# FiltroRecuperador.net
KiCad netlist of a schematic drawn in Altium Designer
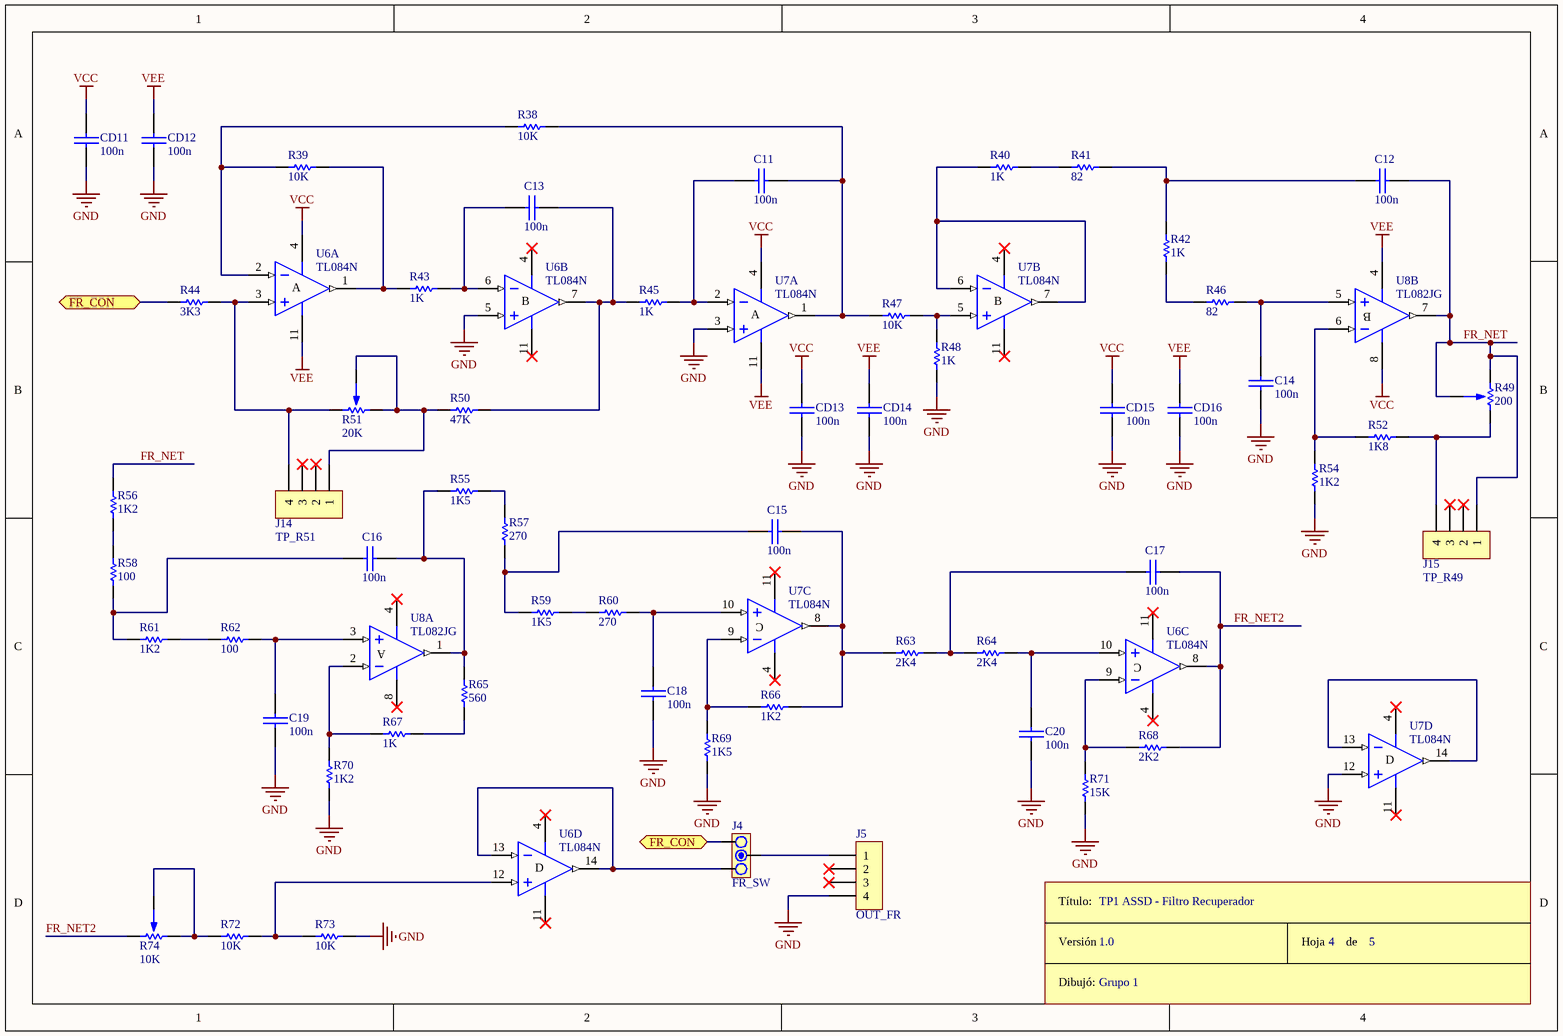
[diagram p0: FiltroRecuperador.SchDoc]

(export (version "E")
  (design (tool "Eeschema 10.0.6"))
  (components
    (comp (ref "C11") (value "100n") (footprint "CAP100") (libsource (lib "LIBEBAL") (part "CAP")))
    (comp (ref "C12") (value "100n") (footprint "CAP100") (libsource (lib "LIBEBAL") (part "CAP")))
    (comp (ref "C13") (value "100n") (footprint "CAP100") (libsource (lib "LIBEBAL") (part "CAP")))
    (comp (ref "C14") (value "100n") (footprint "CAP100") (libsource (lib "LIBEBAL") (part "CAP")))
    (comp (ref "C15") (value "100n") (footprint "CAP100") (libsource (lib "LIBEBAL") (part "CAP")))
    (comp (ref "C16") (value "100n") (footprint "CAP100") (libsource (lib "LIBEBAL") (part "CAP")))
    (comp (ref "C17") (value "100n") (footprint "CAP100") (libsource (lib "LIBEBAL") (part "CAP")))
    (comp (ref "C18") (value "100n") (footprint "CAP100") (libsource (lib "LIBEBAL") (part "CAP")))
    (comp (ref "C19") (value "100n") (footprint "CAP100") (libsource (lib "LIBEBAL") (part "CAP")))
    (comp (ref "C20") (value "100n") (footprint "CAP100") (libsource (lib "LIBEBAL") (part "CAP")))
    (comp (ref "CD11") (value "100n") (footprint "CAP100") (libsource (lib "LIBEBAL") (part "CAP")))
    (comp (ref "CD12") (value "100n") (footprint "CAP100") (libsource (lib "LIBEBAL") (part "CAP")))
    (comp (ref "CD13") (value "100n") (footprint "CAP100") (libsource (lib "LIBEBAL") (part "CAP")))
    (comp (ref "CD14") (value "100n") (footprint "CAP100") (libsource (lib "LIBEBAL") (part "CAP")))
    (comp (ref "CD15") (value "100n") (footprint "CAP100") (libsource (lib "LIBEBAL") (part "CAP")))
    (comp (ref "CD16") (value "100n") (footprint "CAP100") (libsource (lib "LIBEBAL") (part "CAP")))
    (comp (ref "J4") (value "FR_SW") (footprint "JUMPER3") (libsource (lib "LIBEBAL") (part "JUMPER3")))
    (comp (ref "J5") (value "OUT_FR") (footprint "SIP4") (libsource (lib "LIBEBAL") (part "CON4")))
    (comp (ref "J14") (value "TP_R51") (footprint "SIP4") (libsource (lib "") (part "CON4_1")))
    (comp (ref "J15") (value "TP_R49") (footprint "SIP4") (libsource (lib "") (part "CON4_1")))
    (comp (ref "R38") (value "10K") (footprint "RES400") (libsource (lib "LIBEBAL") (part "RES")))
    (comp (ref "R39") (value "10K") (footprint "RES400") (libsource (lib "LIBEBAL") (part "RES")))
    (comp (ref "R40") (value "1K") (footprint "RES400") (libsource (lib "LIBEBAL") (part "RES")))
    (comp (ref "R41") (value "82") (footprint "RES400") (libsource (lib "LIBEBAL") (part "RES")))
    (comp (ref "R42") (value "1K") (footprint "RES400") (libsource (lib "LIBEBAL") (part "RES")))
    (comp (ref "R43") (value "1K") (footprint "RES400") (libsource (lib "LIBEBAL") (part "RES")))
    (comp (ref "R44") (value "3K3") (footprint "RES400") (libsource (lib "LIBEBAL") (part "RES")))
    (comp (ref "R45") (value "1K") (footprint "RES400") (libsource (lib "LIBEBAL") (part "RES")))
    (comp (ref "R46") (value "82") (footprint "RES400") (libsource (lib "LIBEBAL") (part "RES")))
    (comp (ref "R47") (value "10K") (footprint "RES400") (libsource (lib "LIBEBAL") (part "RES")))
    (comp (ref "R48") (value "1K") (footprint "RES400") (libsource (lib "LIBEBAL") (part "RES")))
    (comp (ref "R49") (value "200") (footprint "PRESET V") (libsource (lib "LIBEBAL") (part "PRESET")))
    (comp (ref "R50") (value "47K") (footprint "RES400") (libsource (lib "LIBEBAL") (part "RES")))
    (comp (ref "R51") (value "20K") (footprint "PRESET V") (libsource (lib "LIBEBAL") (part "PRESET")))
    (comp (ref "R52") (value "1K8") (footprint "RES400") (libsource (lib "LIBEBAL") (part "RES")))
    (comp (ref "R54") (value "1K2") (footprint "RES400") (libsource (lib "LIBEBAL") (part "RES")))
    (comp (ref "R55") (value "1K5") (footprint "RES400") (libsource (lib "LIBEBAL") (part "RES")))
    (comp (ref "R56") (value "1K2") (footprint "RES400") (libsource (lib "LIBEBAL") (part "RES")))
    (comp (ref "R57") (value "270") (footprint "RES400") (libsource (lib "LIBEBAL") (part "RES")))
    (comp (ref "R58") (value "100") (footprint "RES400") (libsource (lib "LIBEBAL") (part "RES")))
    (comp (ref "R59") (value "1K5") (footprint "RES400") (libsource (lib "LIBEBAL") (part "RES")))
    (comp (ref "R60") (value "270") (footprint "RES400") (libsource (lib "LIBEBAL") (part "RES")))
    (comp (ref "R61") (value "1K2") (footprint "RES400") (libsource (lib "LIBEBAL") (part "RES")))
    (comp (ref "R62") (value "100") (footprint "RES400") (libsource (lib "LIBEBAL") (part "RES")))
    (comp (ref "R63") (value "2K4") (footprint "RES400") (libsource (lib "LIBEBAL") (part "RES")))
    (comp (ref "R64") (value "2K4") (footprint "RES400") (libsource (lib "LIBEBAL") (part "RES")))
    (comp (ref "R65") (value "560") (footprint "RES400") (libsource (lib "LIBEBAL") (part "RES")))
    (comp (ref "R66") (value "1K2") (footprint "RES400") (libsource (lib "LIBEBAL") (part "RES")))
    (comp (ref "R67") (value "1K") (footprint "RES400") (libsource (lib "LIBEBAL") (part "RES")))
    (comp (ref "R68") (value "2K2") (footprint "RES400") (libsource (lib "LIBEBAL") (part "RES")))
    (comp (ref "R69") (value "1K5") (footprint "RES400") (libsource (lib "LIBEBAL") (part "RES")))
    (comp (ref "R70") (value "1K2") (footprint "RES400") (libsource (lib "LIBEBAL") (part "RES")))
    (comp (ref "R71") (value "15K") (footprint "RES400") (libsource (lib "LIBEBAL") (part "RES")))
    (comp (ref "R72") (value "10K") (footprint "RES400") (libsource (lib "LIBEBAL") (part "RES")))
    (comp (ref "R73") (value "10K") (footprint "RES400") (libsource (lib "LIBEBAL") (part "RES")))
    (comp (ref "R74") (value "10K") (footprint "PRESET V") (libsource (lib "LIBEBAL") (part "PRESET")))
    (comp (ref "ROT4") (value "Rótulo") (libsource (lib "LIB PIO IX") (part "Rótulo")))
    (comp (ref "U6")
      (value "TL084N")
      (footprint "N014")
      (description "JFET-Input Operational Amplifier")
      (fields (field (name "PUBLISHER") "Altium Limited"))
      (libsource (lib "TI Operational Amplifier") (part "TL084N"))
    )
    (comp (ref "U7")
      (value "TL084N")
      (footprint "N014")
      (description "JFET-Input Operational Amplifier")
      (fields (field (name "PUBLISHER") "Altium Limited"))
      (libsource (lib "TI Operational Amplifier") (part "TL084N"))
    )
    (comp (ref "U8")
      (value "TL082JG")
      (footprint "JG008")
      (description "JFET-Input Operational Amplifier")
      (fields (field (name "PUBLISHER") "Altium Limited"))
      (libsource (lib "TI Operational Amplifier") (part "TL082JG"))
    )
  )
  (nets
    (net (code "1") (name "/FR_CON") (class "Default")
      (node (ref "J4") (pin "3") (pinfunction "3_3") (pintype "passive"))
      (node (ref "R44") (pin "1") (pinfunction "1_1") (pintype "passive"))
    )
    (net (code "2") (name "/FR_NET") (class "Default")
      (node (ref "C12") (pin "2") (pinfunction "2_2") (pintype "passive"))
      (node (ref "J15") (pin "1") (pinfunction "1_1") (pintype "passive"))
      (node (ref "R49") (pin "2") (pinfunction "2_2") (pintype "passive"))
      (node (ref "R49") (pin "3") (pinfunction "3_3") (pintype "passive"))
      (node (ref "R56") (pin "1") (pinfunction "1_1") (pintype "passive"))
      (node (ref "U8") (pin "7") (pinfunction "OUT_7") (pintype "output"))
    )
    (net (code "3") (name "/FR_NET2") (class "Default")
      (node (ref "C17") (pin "2") (pinfunction "2_2") (pintype "passive"))
      (node (ref "R68") (pin "2") (pinfunction "2_2") (pintype "passive"))
      (node (ref "R74") (pin "1") (pinfunction "1_1") (pintype "passive"))
      (node (ref "U6") (pin "8") (pinfunction "OUT_8") (pintype "output"))
    )
    (net (code "4") (name "GND") (class "Default")
      (node (ref "C14") (pin "2") (pinfunction "2_2") (pintype "passive"))
      (node (ref "C18") (pin "2") (pinfunction "2_2") (pintype "passive"))
      (node (ref "C19") (pin "1") (pinfunction "1_1") (pintype "passive"))
      (node (ref "C20") (pin "2") (pinfunction "2_2") (pintype "passive"))
      (node (ref "CD11") (pin "2") (pinfunction "2_2") (pintype "passive"))
      (node (ref "CD12") (pin "2") (pinfunction "2_2") (pintype "passive"))
      (node (ref "CD13") (pin "2") (pinfunction "2_2") (pintype "passive"))
      (node (ref "CD14") (pin "2") (pinfunction "2_2") (pintype "passive"))
      (node (ref "CD15") (pin "2") (pinfunction "2_2") (pintype "passive"))
      (node (ref "CD16") (pin "2") (pinfunction "2_2") (pintype "passive"))
      (node (ref "J5") (pin "4") (pinfunction "4_4") (pintype "passive"))
      (node (ref "R48") (pin "1") (pinfunction "1_1") (pintype "passive"))
      (node (ref "R54") (pin "1") (pinfunction "1_1") (pintype "passive"))
      (node (ref "R69") (pin "1") (pinfunction "1_1") (pintype "passive"))
      (node (ref "R70") (pin "1") (pinfunction "1_1") (pintype "passive"))
      (node (ref "R71") (pin "1") (pinfunction "1_1") (pintype "passive"))
      (node (ref "R73") (pin "1") (pinfunction "1_1") (pintype "passive"))
      (node (ref "U6") (pin "5") (pinfunction "IN+_5") (pintype "input"))
      (node (ref "U7") (pin "12") (pinfunction "IN+_12") (pintype "input"))
      (node (ref "U7") (pin "3") (pinfunction "IN+_3") (pintype "input"))
    )
    (net (code "5") (name "Net-(C12-Pad1)") (class "Default")
      (node (ref "C12") (pin "1") (pinfunction "1_1") (pintype "passive"))
      (node (ref "R41") (pin "2") (pinfunction "2_2") (pintype "passive"))
      (node (ref "R42") (pin "2") (pinfunction "2_2") (pintype "passive"))
    )
    (net (code "6") (name "Net-(C15-Pad1)") (class "Default")
      (node (ref "C15") (pin "1") (pinfunction "1_1") (pintype "passive"))
      (node (ref "R57") (pin "2") (pinfunction "2_2") (pintype "passive"))
      (node (ref "R59") (pin "1") (pinfunction "1_1") (pintype "passive"))
    )
    (net (code "7") (name "Net-(C16-Pad1)") (class "Default")
      (node (ref "C16") (pin "1") (pinfunction "1_1") (pintype "passive"))
      (node (ref "R58") (pin "2") (pinfunction "2_2") (pintype "passive"))
      (node (ref "R61") (pin "1") (pinfunction "1_1") (pintype "passive"))
    )
    (net (code "8") (name "Net-(C17-Pad1)") (class "Default")
      (node (ref "C17") (pin "1") (pinfunction "1_1") (pintype "passive"))
      (node (ref "R63") (pin "2") (pinfunction "2_2") (pintype "passive"))
      (node (ref "R64") (pin "1") (pinfunction "1_1") (pintype "passive"))
    )
    (net (code "9") (name "Net-(J4-Pad2)") (class "Default")
      (node (ref "J4") (pin "2") (pinfunction "2_2") (pintype "passive"))
      (node (ref "J5") (pin "1") (pinfunction "1_1") (pintype "passive"))
    )
    (net (code "10") (name "Net-(J14-Pad1)") (class "Default")
      (node (ref "J14") (pin "1") (pinfunction "1_1") (pintype "passive"))
      (node (ref "R50") (pin "1") (pinfunction "1_1") (pintype "passive"))
      (node (ref "R51") (pin "2") (pinfunction "2_2") (pintype "passive"))
      (node (ref "R51") (pin "3") (pinfunction "3_3") (pintype "passive"))
    )
    (net (code "11") (name "Net-(J15-Pad4)") (class "Default")
      (node (ref "J15") (pin "4") (pinfunction "4_4") (pintype "passive"))
      (node (ref "R49") (pin "1") (pinfunction "1_1") (pintype "passive"))
      (node (ref "R52") (pin "2") (pinfunction "2_2") (pintype "passive"))
    )
    (net (code "12") (name "Net-(R40-Pad1)") (class "Default")
      (node (ref "R40") (pin "1") (pinfunction "1_1") (pintype "passive"))
      (node (ref "R41") (pin "1") (pinfunction "1_1") (pintype "passive"))
    )
    (net (code "13") (name "Net-(R42-Pad1)") (class "Default")
      (node (ref "R42") (pin "1") (pinfunction "1_1") (pintype "passive"))
      (node (ref "R46") (pin "1") (pinfunction "1_1") (pintype "passive"))
    )
    (net (code "14") (name "Net-(R55-Pad1)") (class "Default")
      (node (ref "R55") (pin "1") (pinfunction "1_1") (pintype "passive"))
      (node (ref "R57") (pin "1") (pinfunction "1_1") (pintype "passive"))
    )
    (net (code "15") (name "Net-(R56-Pad2)") (class "Default")
      (node (ref "R56") (pin "2") (pinfunction "2_2") (pintype "passive"))
      (node (ref "R58") (pin "1") (pinfunction "1_1") (pintype "passive"))
    )
    (net (code "16") (name "Net-(R59-Pad2)") (class "Default")
      (node (ref "R59") (pin "2") (pinfunction "2_2") (pintype "passive"))
      (node (ref "R60") (pin "1") (pinfunction "1_1") (pintype "passive"))
    )
    (net (code "17") (name "Net-(R61-Pad2)") (class "Default")
      (node (ref "R61") (pin "2") (pinfunction "2_2") (pintype "passive"))
      (node (ref "R62") (pin "1") (pinfunction "1_1") (pintype "passive"))
    )
    (net (code "18") (name "Net-(R65-Pad1)") (class "Default")
      (node (ref "R65") (pin "1") (pinfunction "1_1") (pintype "passive"))
      (node (ref "R67") (pin "2") (pinfunction "2_2") (pintype "passive"))
    )
    (net (code "19") (name "Net-(R72-Pad1)") (class "Default")
      (node (ref "R72") (pin "1") (pinfunction "1_1") (pintype "passive"))
      (node (ref "R74") (pin "2") (pinfunction "2_2") (pintype "passive"))
      (node (ref "R74") (pin "3") (pinfunction "3_3") (pintype "passive"))
    )
    (net (code "20") (name "Net-(U6A-IN+)") (class "Default")
      (node (ref "J14") (pin "4") (pinfunction "4_4") (pintype "passive"))
      (node (ref "R44") (pin "2") (pinfunction "2_2") (pintype "passive"))
      (node (ref "R51") (pin "1") (pinfunction "1_1") (pintype "passive"))
      (node (ref "U6") (pin "3") (pinfunction "IN+_3") (pintype "input"))
    )
    (net (code "21") (name "Net-(U6A-IN-)") (class "Default")
      (node (ref "R38") (pin "1") (pinfunction "1_1") (pintype "passive"))
      (node (ref "R39") (pin "1") (pinfunction "1_1") (pintype "passive"))
      (node (ref "U6") (pin "2") (pinfunction "IN-_2") (pintype "input"))
    )
    (net (code "22") (name "Net-(U6A-OUT)") (class "Default")
      (node (ref "R39") (pin "2") (pinfunction "2_2") (pintype "passive"))
      (node (ref "R43") (pin "1") (pinfunction "1_1") (pintype "passive"))
      (node (ref "U6") (pin "1") (pinfunction "OUT_1") (pintype "output"))
    )
    (net (code "23") (name "Net-(U6B-IN-)") (class "Default")
      (node (ref "C13") (pin "1") (pinfunction "1_1") (pintype "passive"))
      (node (ref "R43") (pin "2") (pinfunction "2_2") (pintype "passive"))
      (node (ref "U6") (pin "6") (pinfunction "IN-_6") (pintype "input"))
    )
    (net (code "24") (name "Net-(U6B-OUT)") (class "Default")
      (node (ref "C13") (pin "2") (pinfunction "2_2") (pintype "passive"))
      (node (ref "R45") (pin "1") (pinfunction "1_1") (pintype "passive"))
      (node (ref "R50") (pin "2") (pinfunction "2_2") (pintype "passive"))
      (node (ref "U6") (pin "7") (pinfunction "OUT_7") (pintype "output"))
    )
    (net (code "25") (name "Net-(U6C-IN+)") (class "Default")
      (node (ref "C20") (pin "1") (pinfunction "1_1") (pintype "passive"))
      (node (ref "R64") (pin "2") (pinfunction "2_2") (pintype "passive"))
      (node (ref "U6") (pin "10") (pinfunction "IN+_10") (pintype "input"))
    )
    (net (code "26") (name "Net-(U6C-IN-)") (class "Default")
      (node (ref "R68") (pin "1") (pinfunction "1_1") (pintype "passive"))
      (node (ref "R71") (pin "2") (pinfunction "2_2") (pintype "passive"))
      (node (ref "U6") (pin "9") (pinfunction "IN-_9") (pintype "input"))
    )
    (net (code "27") (name "Net-(U6D-IN+)") (class "Default")
      (node (ref "R72") (pin "2") (pinfunction "2_2") (pintype "passive"))
      (node (ref "R73") (pin "2") (pinfunction "2_2") (pintype "passive"))
      (node (ref "U6") (pin "12") (pinfunction "IN+_12") (pintype "input"))
    )
    (net (code "28") (name "Net-(U6D-IN-)") (class "Default")
      (node (ref "J4") (pin "1") (pinfunction "1_1") (pintype "passive"))
      (node (ref "U6") (pin "13") (pinfunction "IN-_13") (pintype "input"))
      (node (ref "U6") (pin "14") (pinfunction "OUT_14") (pintype "output"))
    )
    (net (code "29") (name "Net-(U7A-IN-)") (class "Default")
      (node (ref "C11") (pin "1") (pinfunction "1_1") (pintype "passive"))
      (node (ref "R45") (pin "2") (pinfunction "2_2") (pintype "passive"))
      (node (ref "U7") (pin "2") (pinfunction "IN-_2") (pintype "input"))
    )
    (net (code "30") (name "Net-(U7A-OUT)") (class "Default")
      (node (ref "C11") (pin "2") (pinfunction "2_2") (pintype "passive"))
      (node (ref "R38") (pin "2") (pinfunction "2_2") (pintype "passive"))
      (node (ref "R47") (pin "1") (pinfunction "1_1") (pintype "passive"))
      (node (ref "U7") (pin "1") (pinfunction "OUT_1") (pintype "output"))
    )
    (net (code "31") (name "Net-(U7B-IN+)") (class "Default")
      (node (ref "R47") (pin "2") (pinfunction "2_2") (pintype "passive"))
      (node (ref "R48") (pin "2") (pinfunction "2_2") (pintype "passive"))
      (node (ref "U7") (pin "5") (pinfunction "IN+_5") (pintype "input"))
    )
    (net (code "32") (name "Net-(U7B-IN-)") (class "Default")
      (node (ref "R40") (pin "2") (pinfunction "2_2") (pintype "passive"))
      (node (ref "U7") (pin "6") (pinfunction "IN-_6") (pintype "input"))
      (node (ref "U7") (pin "7") (pinfunction "OUT_7") (pintype "output"))
    )
    (net (code "33") (name "Net-(U7C-IN+)") (class "Default")
      (node (ref "C18") (pin "1") (pinfunction "1_1") (pintype "passive"))
      (node (ref "R60") (pin "2") (pinfunction "2_2") (pintype "passive"))
      (node (ref "U7") (pin "10") (pinfunction "IN+_10") (pintype "input"))
    )
    (net (code "34") (name "Net-(U7C-IN-)") (class "Default")
      (node (ref "R66") (pin "1") (pinfunction "1_1") (pintype "passive"))
      (node (ref "R69") (pin "2") (pinfunction "2_2") (pintype "passive"))
      (node (ref "U7") (pin "9") (pinfunction "IN-_9") (pintype "input"))
    )
    (net (code "35") (name "Net-(U7C-OUT)") (class "Default")
      (node (ref "C15") (pin "2") (pinfunction "2_2") (pintype "passive"))
      (node (ref "R63") (pin "1") (pinfunction "1_1") (pintype "passive"))
      (node (ref "R66") (pin "2") (pinfunction "2_2") (pintype "passive"))
      (node (ref "U7") (pin "8") (pinfunction "OUT_8") (pintype "output"))
    )
    (net (code "36") (name "Net-(U7D-IN-)") (class "Default")
      (node (ref "U7") (pin "13") (pinfunction "IN-_13") (pintype "input"))
      (node (ref "U7") (pin "14") (pinfunction "OUT_14") (pintype "output"))
    )
    (net (code "37") (name "Net-(U8A-IN+)") (class "Default")
      (node (ref "C19") (pin "2") (pinfunction "2_2") (pintype "passive"))
      (node (ref "R62") (pin "2") (pinfunction "2_2") (pintype "passive"))
      (node (ref "U8") (pin "3") (pinfunction "IN+_3") (pintype "input"))
    )
    (net (code "38") (name "Net-(U8A-IN-)") (class "Default")
      (node (ref "R67") (pin "1") (pinfunction "1_1") (pintype "passive"))
      (node (ref "R70") (pin "2") (pinfunction "2_2") (pintype "passive"))
      (node (ref "U8") (pin "2") (pinfunction "IN-_2") (pintype "input"))
    )
    (net (code "39") (name "Net-(U8A-OUT)") (class "Default")
      (node (ref "C16") (pin "2") (pinfunction "2_2") (pintype "passive"))
      (node (ref "R55") (pin "2") (pinfunction "2_2") (pintype "passive"))
      (node (ref "R65") (pin "2") (pinfunction "2_2") (pintype "passive"))
      (node (ref "U8") (pin "1") (pinfunction "OUT_1") (pintype "output"))
    )
    (net (code "40") (name "Net-(U8B-IN+)") (class "Default")
      (node (ref "C14") (pin "1") (pinfunction "1_1") (pintype "passive"))
      (node (ref "R46") (pin "2") (pinfunction "2_2") (pintype "passive"))
      (node (ref "U8") (pin "5") (pinfunction "IN+_5") (pintype "input"))
    )
    (net (code "41") (name "Net-(U8B-IN-)") (class "Default")
      (node (ref "R52") (pin "1") (pinfunction "1_1") (pintype "passive"))
      (node (ref "R54") (pin "2") (pinfunction "2_2") (pintype "passive"))
      (node (ref "U8") (pin "6") (pinfunction "IN-_6") (pintype "input"))
    )
    (net (code "42") (name "VCC") (class "Default")
      (node (ref "CD11") (pin "1") (pinfunction "1_1") (pintype "passive"))
      (node (ref "CD13") (pin "1") (pinfunction "1_1") (pintype "passive"))
      (node (ref "CD15") (pin "1") (pinfunction "1_1") (pintype "passive"))
      (node (ref "U6") (pin "4") (pinfunction "V+_4") (pintype "power_in"))
      (node (ref "U7") (pin "4") (pinfunction "V+_4") (pintype "power_in"))
      (node (ref "U8") (pin "8") (pinfunction "V+_8") (pintype "power_in"))
    )
    (net (code "43") (name "VEE") (class "Default")
      (node (ref "CD12") (pin "1") (pinfunction "1_1") (pintype "passive"))
      (node (ref "CD14") (pin "1") (pinfunction "1_1") (pintype "passive"))
      (node (ref "CD16") (pin "1") (pinfunction "1_1") (pintype "passive"))
      (node (ref "U6") (pin "11") (pinfunction "V-_11") (pintype "power_in"))
      (node (ref "U7") (pin "11") (pinfunction "V-_11") (pintype "power_in"))
      (node (ref "U8") (pin "4") (pinfunction "V-_4") (pintype "power_in"))
    )
    (net (code "44") (name "unconnected-(J5-Pad2)") (class "Default")
      (node (ref "J5") (pin "2") (pinfunction "2_2") (pintype "passive+no_connect"))
    )
    (net (code "45") (name "unconnected-(J5-Pad3)") (class "Default")
      (node (ref "J5") (pin "3") (pinfunction "3_3") (pintype "passive+no_connect"))
    )
    (net (code "46") (name "unconnected-(J14-Pad2)") (class "Default")
      (node (ref "J14") (pin "2") (pinfunction "2_2") (pintype "passive+no_connect"))
    )
    (net (code "47") (name "unconnected-(J14-Pad3)") (class "Default")
      (node (ref "J14") (pin "3") (pinfunction "3_3") (pintype "passive+no_connect"))
    )
    (net (code "48") (name "unconnected-(J15-Pad2)") (class "Default")
      (node (ref "J15") (pin "2") (pinfunction "2_2") (pintype "passive+no_connect"))
    )
    (net (code "49") (name "unconnected-(J15-Pad3)") (class "Default")
      (node (ref "J15") (pin "3") (pinfunction "3_3") (pintype "passive+no_connect"))
    )
    (net (code "50") (name "unconnected-(U6B-V+-Pad4)") (class "Default")
      (node (ref "U6") (pin "4") (pinfunction "V+_4") (pintype "power_in+no_connect"))
    )
    (net (code "51") (name "unconnected-(U6B-V--Pad11)") (class "Default")
      (node (ref "U6") (pin "11") (pinfunction "V-_11") (pintype "power_in+no_connect"))
    )
    (net (code "52") (name "unconnected-(U6C-V+-Pad4)") (class "Default")
      (node (ref "U6") (pin "4") (pinfunction "V+_4") (pintype "power_in+no_connect"))
    )
    (net (code "53") (name "unconnected-(U6C-V--Pad11)") (class "Default")
      (node (ref "U6") (pin "11") (pinfunction "V-_11") (pintype "power_in+no_connect"))
    )
    (net (code "54") (name "unconnected-(U6D-V+-Pad4)") (class "Default")
      (node (ref "U6") (pin "4") (pinfunction "V+_4") (pintype "power_in+no_connect"))
    )
    (net (code "55") (name "unconnected-(U6D-V--Pad11)") (class "Default")
      (node (ref "U6") (pin "11") (pinfunction "V-_11") (pintype "power_in+no_connect"))
    )
    (net (code "56") (name "unconnected-(U7B-V+-Pad4)") (class "Default")
      (node (ref "U7") (pin "4") (pinfunction "V+_4") (pintype "power_in+no_connect"))
    )
    (net (code "57") (name "unconnected-(U7B-V--Pad11)") (class "Default")
      (node (ref "U7") (pin "11") (pinfunction "V-_11") (pintype "power_in+no_connect"))
    )
    (net (code "58") (name "unconnected-(U7C-V+-Pad4)") (class "Default")
      (node (ref "U7") (pin "4") (pinfunction "V+_4") (pintype "power_in+no_connect"))
    )
    (net (code "59") (name "unconnected-(U7C-V--Pad11)") (class "Default")
      (node (ref "U7") (pin "11") (pinfunction "V-_11") (pintype "power_in+no_connect"))
    )
    (net (code "60") (name "unconnected-(U7D-V+-Pad4)") (class "Default")
      (node (ref "U7") (pin "4") (pinfunction "V+_4") (pintype "power_in+no_connect"))
    )
    (net (code "61") (name "unconnected-(U7D-V--Pad11)") (class "Default")
      (node (ref "U7") (pin "11") (pinfunction "V-_11") (pintype "power_in+no_connect"))
    )
    (net (code "62") (name "unconnected-(U8A-V+-Pad8)") (class "Default")
      (node (ref "U8") (pin "8") (pinfunction "V+_8") (pintype "power_in+no_connect"))
    )
    (net (code "63") (name "unconnected-(U8A-V--Pad4)") (class "Default")
      (node (ref "U8") (pin "4") (pinfunction "V-_4") (pintype "power_in+no_connect"))
    )
  )
)
